# TIDA-01576_ADS8686S_AFE_Pg3-eFuse_3_3V_D.net
KiCad netlist of a schematic drawn in Altium Designer
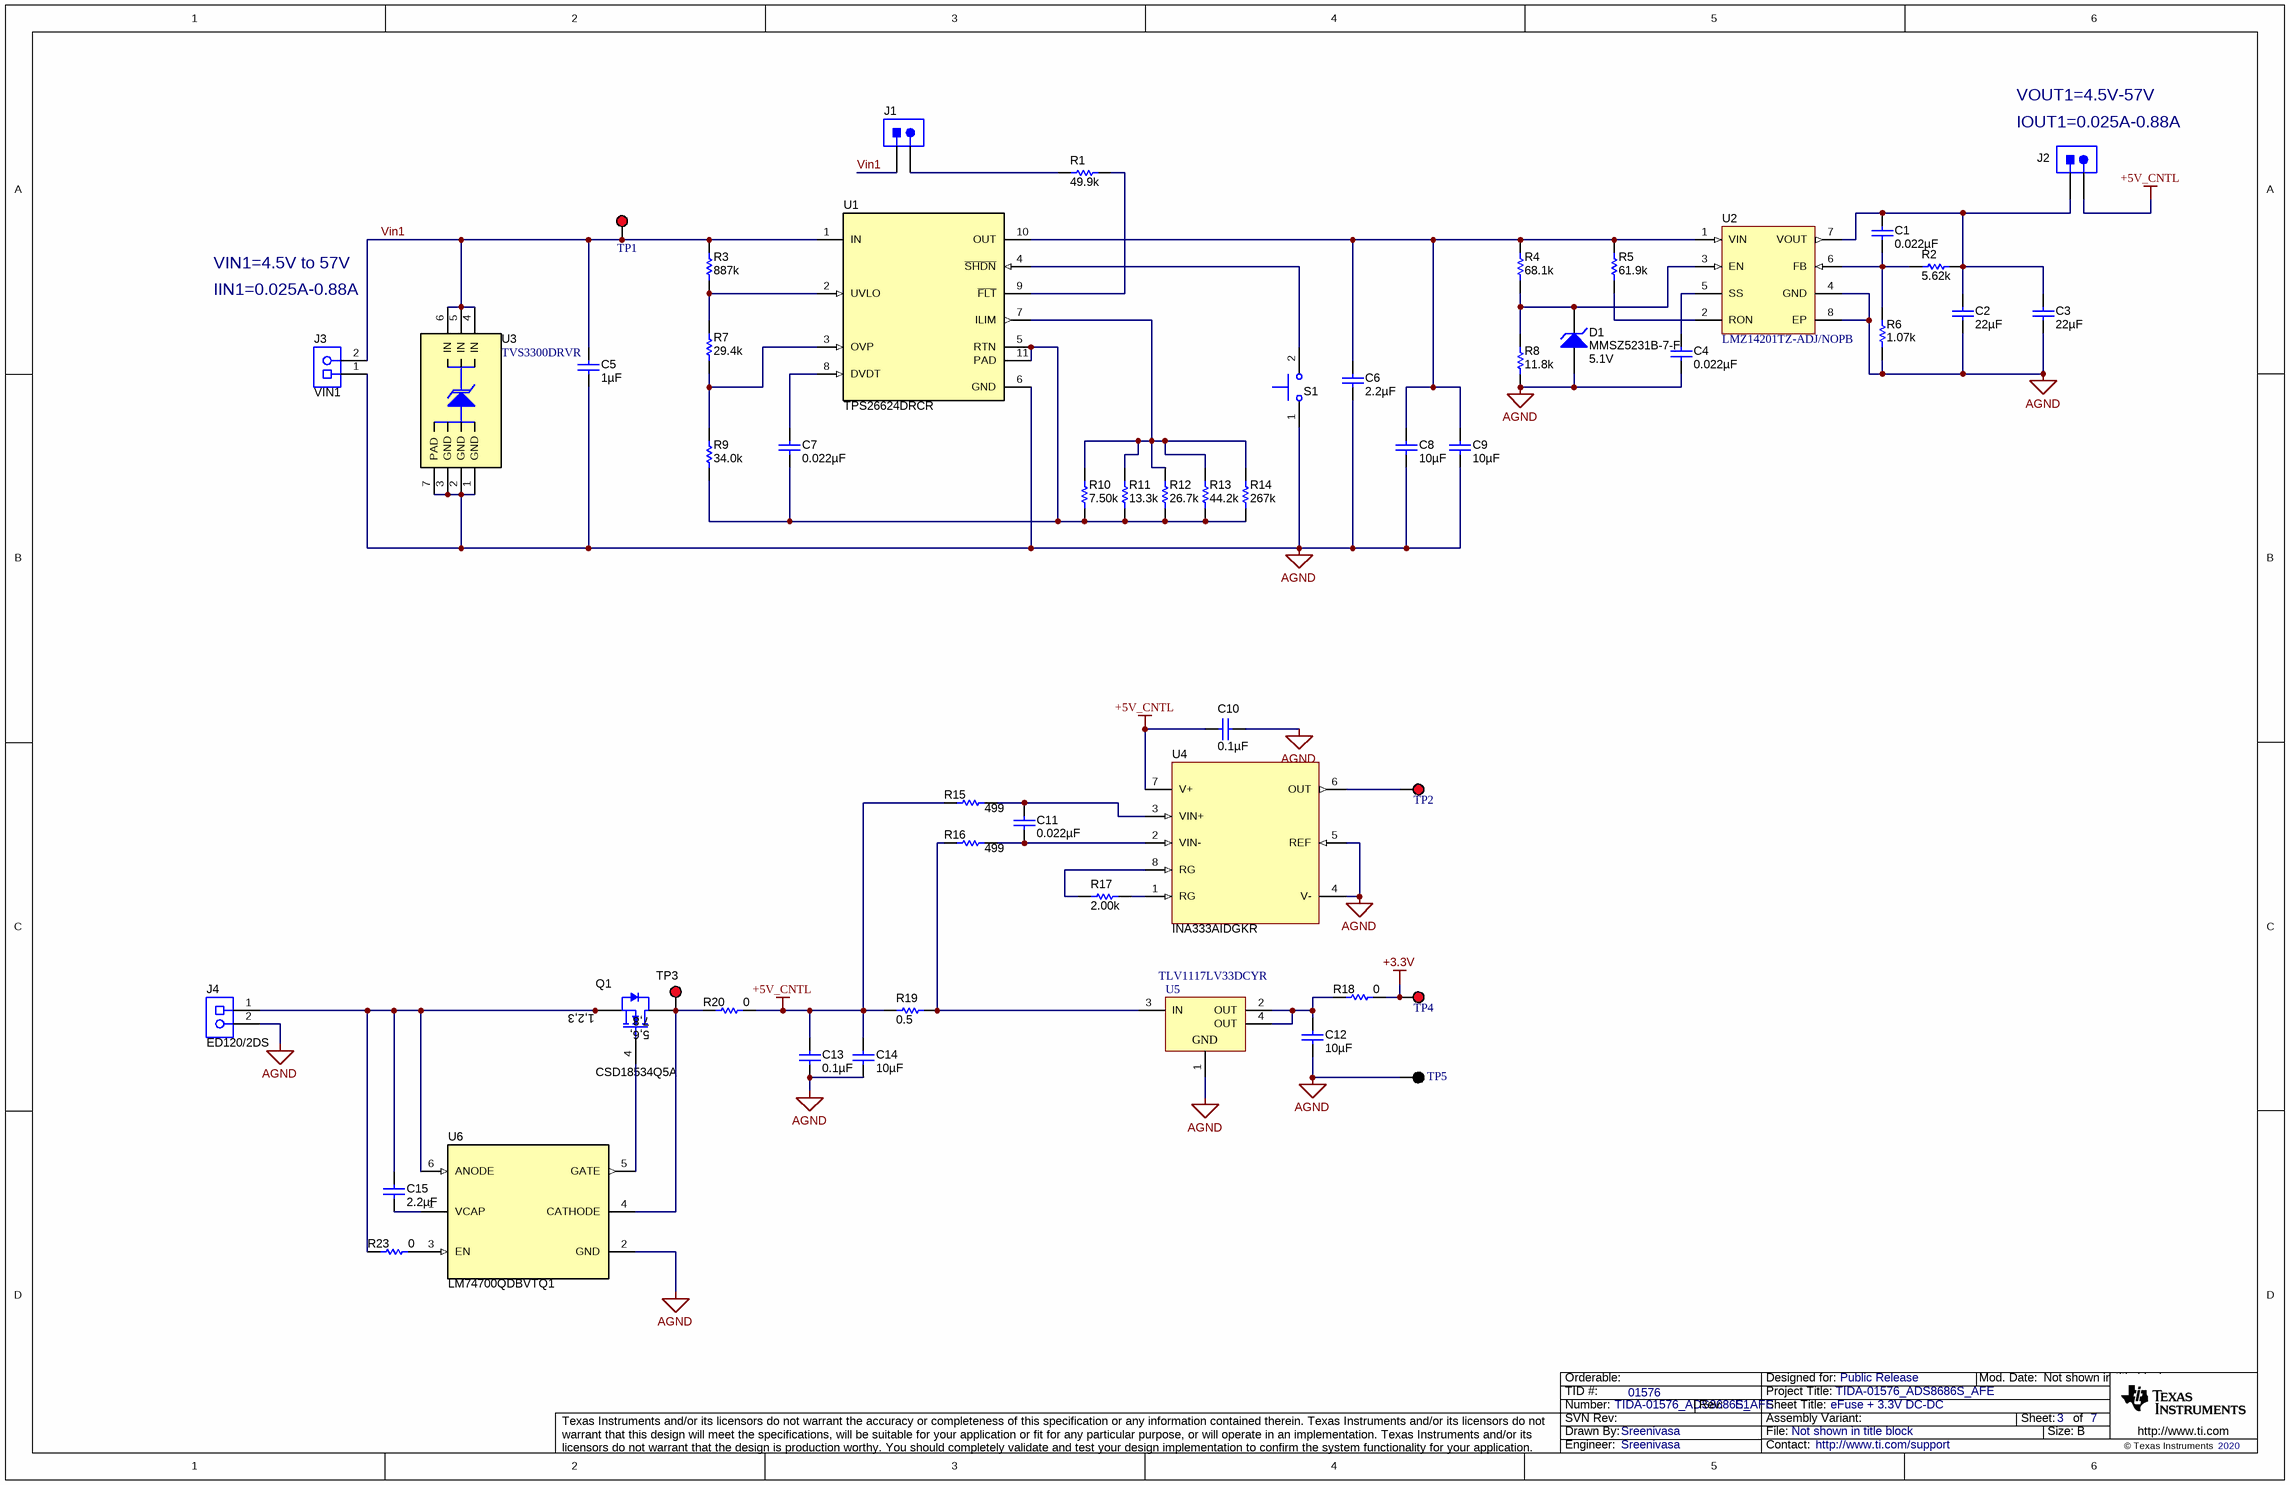
[diagram p0: TIDA-01576_ADS8686S_AFE_Pg3-eFuse + 3.3V DC-DC.SchDoc]

(export (version "E")
  (design (tool "Eeschema 10.0.6"))
  (components
    (comp (ref "C1")
      (value "C0603C223K4RACTU")
      (footprint "0603")
      (description "CAP, CERM, 0.022 µF, 16 V,+/- 10%, X7R, 0603")
      (fields
        (field (name "VALUEDISPLAYED") "0.022µF")
        (field (name "MANUFACTURER") "Kemet")
        (field (name "PUBLISHER") "Texas Instruments")
      )
      (libsource (lib "Capacitor_Ceramic") (part "C0603C223K4RACTU"))
    )
    (comp (ref "C2")
      (value "EMK316BB7226ML-T")
      (footprint "1206_190")
      (description "CAP, CERM, 22 µF, 16 V,+/- 20%, X7R, 1206")
      (fields
        (field (name "VALUEDISPLAYED") "22µF")
        (field (name "MANUFACTURER") "Taiyo Yuden")
        (field (name "PUBLISHER") "Texas Instruments")
      )
      (libsource (lib "Capacitor_Ceramic") (part "EMK316BB7226ML-T"))
    )
    (comp (ref "C3")
      (value "EMK316BB7226ML-T")
      (footprint "1206_190")
      (description "CAP, CERM, 22 µF, 16 V,+/- 20%, X7R, 1206")
      (fields
        (field (name "VALUEDISPLAYED") "22µF")
        (field (name "MANUFACTURER") "Taiyo Yuden")
        (field (name "PUBLISHER") "Texas Instruments")
      )
      (libsource (lib "Capacitor_Ceramic") (part "EMK316BB7226ML-T"))
    )
    (comp (ref "C4")
      (value "C0603C223K4RACTU")
      (footprint "0603")
      (description "CAP, CERM, 0.022 µF, 16 V,+/- 10%, X7R, 0603")
      (fields
        (field (name "VALUEDISPLAYED") "0.022µF")
        (field (name "MANUFACTURER") "Kemet")
        (field (name "PUBLISHER") "Texas Instruments")
      )
      (libsource (lib "Capacitor_Ceramic") (part "C0603C223K4RACTU"))
    )
    (comp (ref "C5")
      (value "GRM31CR72A105KA01L")
      (footprint "1206_180M")
      (description "CAP, CERM, 1 µF, 100 V, +/- 10%, X7R, 1206")
      (fields
        (field (name "VALUEDISPLAYED") "1µF")
        (field (name "MANUFACTURER") "MuRata")
        (field (name "PUBLISHER") "Texas Instruments")
      )
      (libsource (lib "Capacitor_Ceramic") (part "GRM31CR72A105KA01L"))
    )
    (comp (ref "C6")
      (value "GRM32ER72A225KA35L")
      (footprint "1210_270")
      (description "CAP, CERM, 2.2 µF, 100 V, +/- 10%, X7R, 1210")
      (fields
        (field (name "VALUEDISPLAYED") "2.2µF")
        (field (name "MANUFACTURER") "MuRata")
        (field (name "PUBLISHER") "Texas Instruments")
      )
      (libsource (lib "Capacitor_Ceramic") (part "GRM32ER72A225KA35L"))
    )
    (comp (ref "C7")
      (value "GRM188R71C223KA01D")
      (footprint "0603")
      (description "CAP, CERM, 0.022 µF, 16 V,+/- 10%, X7R, 0603")
      (fields
        (field (name "VALUEDISPLAYED") "0.022µF")
        (field (name "MANUFACTURER") "MuRata")
        (field (name "PUBLISHER") "Texas Instruments")
      )
      (libsource (lib "Capacitor_Ceramic") (part "GRM188R71C223KA01D"))
    )
    (comp (ref "C8")
      (value "GRM32ER71J106KA12L")
      (footprint "1210_270")
      (description "CAP, CERM, 10 µF, 63 V, +/- 10%, X7R, 1210")
      (fields
        (field (name "VALUEDISPLAYED") "10µF")
        (field (name "MANUFACTURER") "MuRata")
        (field (name "PUBLISHER") "Texas Instruments")
      )
      (libsource (lib "Capacitor_Ceramic") (part "GRM32ER71J106KA12L"))
    )
    (comp (ref "C9")
      (value "GRM32ER71J106KA12L")
      (footprint "1210_270")
      (description "CAP, CERM, 10 µF, 63 V, +/- 10%, X7R, 1210")
      (fields
        (field (name "VALUEDISPLAYED") "10µF")
        (field (name "MANUFACTURER") "MuRata")
        (field (name "PUBLISHER") "Texas Instruments")
      )
      (libsource (lib "Capacitor_Ceramic") (part "GRM32ER71J106KA12L"))
    )
    (comp (ref "C10")
      (value "06033C104JAT2A")
      (footprint "0603M")
      (description "CAP, CERM, 0.1uF, 25V, +/-5%, X7R, 0603")
      (fields
        (field (name "VALUEDISPLAYED") "0.1µF")
        (field (name "MANUFACTURER") "AVX")
        (field (name "PUBLISHER") "Texas Instruments")
      )
      (libsource (lib "Capacitor_Ceramic") (part "06033C104JAT2A"))
    )
    (comp (ref "C11")
      (value "C0603C223K3RACTU")
      (footprint "0603M")
      (description "CAP, CERM, 0.022uF, 25V, +/-10%, X7R, 0603")
      (fields
        (field (name "VALUEDISPLAYED") "0.022µF")
        (field (name "MANUFACTURER") "Kemet")
        (field (name "PUBLISHER") "Texas Instruments")
      )
      (libsource (lib "Capacitor_Ceramic") (part "C0603C223K3RACTU"))
    )
    (comp (ref "C12")
      (value "C0603C106M9PACTU")
      (footprint "0603")
      (description "CAP, CERM, 10 µF, 6.3 V, +/- 20%, X5R, 0603")
      (fields
        (field (name "VALUEDISPLAYED") "10µF")
        (field (name "MANUFACTURER") "Kemet")
        (field (name "PUBLISHER") "Texas Instruments")
      )
      (libsource (lib "Capacitor_Ceramic") (part "C0603C106M9PACTU"))
    )
    (comp (ref "C13")
      (value "C0603C104K5RACTU")
      (footprint "0603")
      (description "CAP, CERM, 0.1uF, 50V, +/-10%, X7R, 0603")
      (fields
        (field (name "VALUEDISPLAYED") "0.1µF")
        (field (name "MANUFACTURER") "Kemet")
        (field (name "PUBLISHER") "Texas Instruments")
      )
      (libsource (lib "Capacitor_Ceramic") (part "C0603C104K5RACTU"))
    )
    (comp (ref "C14")
      (value "C0603C106M9PACTU")
      (footprint "0603")
      (description "CAP, CERM, 10 µF, 6.3 V, +/- 20%, X5R, 0603")
      (fields
        (field (name "VALUEDISPLAYED") "10µF")
        (field (name "MANUFACTURER") "Kemet")
        (field (name "PUBLISHER") "Texas Instruments")
      )
      (libsource (lib "Capacitor_Ceramic") (part "C0603C106M9PACTU"))
    )
    (comp (ref "C15")
      (value "C0805C225K8RACTU")
      (footprint "0805_HV")
      (description "CAP, CERM, 2.2uF, 10V, +/-10%, X7R, 0805")
      (fields
        (field (name "VALUEDISPLAYED") "2.2µF")
        (field (name "MANUFACTURER") "Kemet")
        (field (name "PUBLISHER") "Texas Instruments")
      )
      (libsource (lib "Capacitor_Ceramic") (part "C0805C225K8RACTU"))
    )
    (comp (ref "D1")
      (value "MMSZ5231B-7-F")
      (footprint "SOD-123")
      (description "Diode, Zener, 5.1 V, 500 mW, SOD-123")
      (fields
        (field (name "ALTIUM_VALUE") "5.1V")
        (field (name "MANUFACTURER") "Diodes Inc.")
        (field (name "SYMBOLCREATOR") "a0412235")
        (field (name "PUBLISHER") "Texas Instruments")
      )
      (libsource (lib "ZenerDiodes") (part "MMSZ5231B-7-F"))
    )
    (comp (ref "J1")
      (value "PBC02SAAN")
      (footprint "Sullins_PBC02SAAN")
      (description "Header, 100mil, 2x1, Gold, TH")
      (fields
        (field (name "MANUFACTURER") "Sullins Connector Solutions")
        (field (name "PUBLISHER") "Texas Instruments")
        (field (name "SYMBOLCREATOR") "a0412235")
      )
      (libsource (lib "Connectors_Sullins") (part "PBC02SAAN"))
    )
    (comp (ref "J2")
      (value "PBC02SAAN")
      (footprint "Sullins_PBC02SAAN")
      (description "Header, 100mil, 2x1, Gold, TH")
      (fields
        (field (name "MANUFACTURER") "Sullins Connector Solutions")
        (field (name "PUBLISHER") "Texas Instruments")
        (field (name "SYMBOLCREATOR") "a0412235")
      )
      (libsource (lib "Connectors_Sullins") (part "PBC02SAAN"))
    )
    (comp (ref "J3")
      (value "VIN1")
      (footprint "TEC_282841-2")
      (description "Terminal Block, 2x1, 5.08mm, TH")
      (fields
        (field (name "MANUFACTURER") "TE Connectivity")
        (field (name "PARTNUMBER") "282841-2")
        (field (name "PUBLISHER") "Texas Instruments")
      )
      (libsource (lib "Altium Vault - TI") (part "CMP-0054973-1"))
    )
    (comp (ref "J4")
      (value "ED120/2DS")
      (footprint "CONN_ED120-2DS")
      (description "TERMINAL BLOCK 5.08MM VERT 2POS, TH")
      (fields
        (field (name "MANUFACTURER") "On-Shore Technology")
        (field (name "SYMBOLCREATOR") "a0412235")
        (field (name "PUBLISHER") "Texas Instruments")
      )
      (libsource (lib "Connectors") (part "ED120/2DS"))
    )
    (comp (ref "Q1")
      (value "CSD18534Q5A")
      (footprint "DQJ0008A")
      (description "MOSFET, N-CH, 60 V, 50 A, DQJ0008A (VSONP-8)")
      (fields
        (field (name "MANUFACTURER") "Texas Instruments")
        (field (name "PUBLISHER") "Texas Instruments")
      )
      (libsource (lib "Altium Vault - TI") (part "CMP-0000817-1"))
    )
    (comp (ref "R1")
      (value "CRCW060349K9FKEA")
      (footprint "0603")
      (description "RES, 49.9 k, 1%, 0.1 W, 0603")
      (fields
        (field (name "MANUFACTURER") "Vishay-Dale")
        (field (name "VALUEDISPLAYED") "49.9k")
        (field (name "PUBLISHER") "Texas Instruments")
      )
      (libsource (lib "Resistor_0603") (part "CRCW060349K9FKEA"))
    )
    (comp (ref "R2")
      (value "RC0603FR-075K62L")
      (footprint "0603")
      (description "RES, 5.62 k, 1%, 0.1 W, 0603")
      (fields
        (field (name "VALUEDISPLAYED") "5.62k")
        (field (name "MANUFACTURER") "Yageo America")
        (field (name "PUBLISHER") "Texas Instruments")
      )
      (libsource (lib "Resistor_0603") (part "RC0603FR-075K62L"))
    )
    (comp (ref "R3")
      (value "CRCW0603887KFKEA")
      (footprint "0603")
      (description "RES, 887 k, 1%, 0.1 W, 0603")
      (fields
        (field (name "VALUEDISPLAYED") "887k")
        (field (name "MANUFACTURER") "Vishay-Dale")
        (field (name "PUBLISHER") "Texas Instruments")
      )
      (libsource (lib "Resistor_0603") (part "CRCW0603887KFKEA"))
    )
    (comp (ref "R4")
      (value "CRCW120668K1FKEA")
      (footprint "1206")
      (description "RES, 68.1 k, 1%, 0.25 W, 1206")
      (fields
        (field (name "VALUEDISPLAYED") "68.1k")
        (field (name "MANUFACTURER") "Vishay-Dale")
        (field (name "PUBLISHER") "Texas Instruments")
      )
      (libsource (lib "Resistor_1206") (part "CRCW120668K1FKEA"))
    )
    (comp (ref "R5")
      (value "RC1206FR-0761K9L")
      (footprint "1206")
      (description "RES, 61.9 k, 1%, 0.25 W, 1206")
      (fields
        (field (name "VALUEDISPLAYED") "61.9k")
        (field (name "MANUFACTURER") "Yageo America")
        (field (name "PUBLISHER") "Texas Instruments")
      )
      (libsource (lib "Resistor_1206") (part "RC1206FR-0761K9L"))
    )
    (comp (ref "R6")
      (value "ERA-3AEB1071V")
      (footprint "0603")
      (description "RES SMD 1.07KOHM 0.1% 1/10W 0603")
      (fields
        (field (name "VALUEDISPLAYED") "1.07k")
        (field (name "MANUFACTURER") "Panasonic")
        (field (name "PUBLISHER") "Texas Instruments")
      )
      (libsource (lib "Resistor_0603") (part "RT0603DRE071K07L"))
    )
    (comp (ref "R7")
      (value "CRCW060329K4FKEA")
      (footprint "0603")
      (description "RES, 29.4 k, 1%, 0.1 W, 0603")
      (fields
        (field (name "VALUEDISPLAYED") "29.4k")
        (field (name "MANUFACTURER") "Vishay-Dale")
        (field (name "PUBLISHER") "Texas Instruments")
      )
      (libsource (lib "Resistor_0603") (part "CRCW060329K4FKEA"))
    )
    (comp (ref "R8")
      (value "CRCW120611K8FKEA")
      (footprint "1206")
      (description "RES, 11.8 k, 1%, 0.25 W, 1206")
      (fields
        (field (name "VALUEDISPLAYED") "11.8k")
        (field (name "MANUFACTURER") "Vishay-Dale")
        (field (name "PUBLISHER") "Texas Instruments")
      )
      (libsource (lib "Resistor_1206") (part "CRCW120611K8FKEA"))
    )
    (comp (ref "R9")
      (value "CRCW060334K0FKEA")
      (footprint "0603")
      (description "RES, 34.0 k, 1%, 0.1 W, 0603")
      (fields
        (field (name "MANUFACTURER") "Vishay-Dale")
        (field (name "VALUEDISPLAYED") "34.0k")
        (field (name "PUBLISHER") "Texas Instruments")
      )
      (libsource (lib "Resistor_0603") (part "CRCW060334K0FKEA"))
    )
    (comp (ref "R10")
      (value "CRCW06037K50FKEA")
      (footprint "0603")
      (description "RES, 7.50 k, 1%, 0.1 W, 0603")
      (fields
        (field (name "VALUEDISPLAYED") "7.50k")
        (field (name "MANUFACTURER") "Vishay-Dale")
        (field (name "PUBLISHER") "Texas Instruments")
      )
      (libsource (lib "Resistor_0603") (part "CRCW06037K50FKEA"))
    )
    (comp (ref "R11")
      (value "CRCW060313K3FKEA")
      (footprint "0603")
      (description "RES, 13.3 k, 1%, 0.1 W, 0603")
      (fields
        (field (name "VALUEDISPLAYED") "13.3k")
        (field (name "MANUFACTURER") "Vishay-Dale")
        (field (name "PUBLISHER") "Texas Instruments")
      )
      (libsource (lib "Resistor_0603") (part "CRCW060313K3FKEA"))
    )
    (comp (ref "R12")
      (value "CRCW060326K7FKEA")
      (footprint "0603")
      (description "RES, 26.7 k, 1%, 0.1 W, 0603")
      (fields
        (field (name "VALUEDISPLAYED") "26.7k")
        (field (name "MANUFACTURER") "Vishay-Dale")
        (field (name "PUBLISHER") "Texas Instruments")
      )
      (libsource (lib "Resistor_0603") (part "CRCW060326K7FKEA"))
    )
    (comp (ref "R13")
      (value "CRCW060344K2FKEA")
      (footprint "0603")
      (description "RES, 44.2 k, 1%, 0.1 W, 0603")
      (fields
        (field (name "VALUEDISPLAYED") "44.2k")
        (field (name "MANUFACTURER") "Vishay-Dale")
        (field (name "PUBLISHER") "Texas Instruments")
      )
      (libsource (lib "Resistor_0603") (part "CRCW060344K2FKEA"))
    )
    (comp (ref "R14")
      (value "CRCW0603267KFKEA")
      (footprint "0603")
      (description "RES, 267 k, 1%, 0.1 W, 0603")
      (fields
        (field (name "VALUEDISPLAYED") "267k")
        (field (name "MANUFACTURER") "Vishay-Dale")
        (field (name "PUBLISHER") "Texas Instruments")
      )
      (libsource (lib "Resistor_0603") (part "CRCW0603267KFKEA"))
    )
    (comp (ref "R15")
      (value "499")
      (footprint "0402M")
      (description "RES, 499 ohm, 1%, 0.063W, 0402")
      (fields
        (field (name "PARTNUMBER") "CRCW0402499RFKED")
        (field (name "MANUFACTURER") "Vishay-Dale")
        (field (name "PUBLISHER") "Texas Instruments")
      )
      (libsource (lib "Resistor_0402") (part "CRCW0402499RFKED"))
    )
    (comp (ref "R16")
      (value "499")
      (footprint "0402M")
      (description "RES, 499 ohm, 1%, 0.063W, 0402")
      (fields
        (field (name "PARTNUMBER") "CRCW0402499RFKED")
        (field (name "MANUFACTURER") "Vishay-Dale")
        (field (name "PUBLISHER") "Texas Instruments")
      )
      (libsource (lib "Resistor_0402") (part "CRCW0402499RFKED"))
    )
    (comp (ref "R17")
      (value "CRCW04022K00FKED")
      (footprint "0402")
      (description "RES, 2.00 k, 1%, 0.063 W, 0402")
      (fields
        (field (name "VALUEDISPLAYED") "2.00k")
        (field (name "MANUFACTURER") "Vishay-Dale")
        (field (name "PUBLISHER") "Texas Instruments")
      )
      (libsource (lib "Resistor_0402") (part "CRCW04022K00FKED"))
    )
    (comp (ref "R18")
      (value "0")
      (footprint "0603")
      (description "RES, 0 ohm, 5%, 0.1W, 0603")
      (fields
        (field (name "PARTNUMBER") "CRCW06030000Z0EA")
        (field (name "MANUFACTURER") "Vishay-Dale")
        (field (name "PUBLISHER") "Texas Instruments")
      )
      (libsource (lib "Resistor_0603") (part "CRCW06030000Z0EA"))
    )
    (comp (ref "R19")
      (value "RL1220S-R50-F")
      (footprint "RL1220")
      (description "RES, 0.5, 1%, 0.33 W, 0805")
      (fields
        (field (name "VALUEDISPLAYED") "0.5")
        (field (name "MANUFACTURER") "Susumu Co Ltd")
        (field (name "PUBLISHER") "Texas Instruments")
      )
      (libsource (lib "Resistor_0805") (part "RL1220S-R50-F"))
    )
    (comp (ref "R20")
      (value "0")
      (footprint "0603")
      (description "RES, 0 ohm, 5%, 0.1W, 0603")
      (fields
        (field (name "PARTNUMBER") "CRCW06030000Z0EA")
        (field (name "MANUFACTURER") "Vishay-Dale")
        (field (name "PUBLISHER") "Texas Instruments")
      )
      (libsource (lib "Resistor_0603") (part "CRCW06030000Z0EA"))
    )
    (comp (ref "R23")
      (value "0")
      (footprint "0603")
      (description "RES, 0 ohm, 5%, 0.1W, 0603")
      (fields
        (field (name "PARTNUMBER") "CRCW06030000Z0EA")
        (field (name "MANUFACTURER") "Vishay-Dale")
        (field (name "PUBLISHER") "Texas Instruments")
      )
      (libsource (lib "Resistor_0603") (part "CRCW06030000Z0EA"))
    )
    (comp (ref "S1")
      (value "PTS820 J20M SMTR LFS")
      (footprint "SW_PTS820")
      (description "Switch, SPST-NO,  Off-Mom, 0.05A, 12VDC, SMD")
      (fields
        (field (name "MANUFACTURER") "C&K Components")
        (field (name "SYMBOLCREATOR") "a0412235")
        (field (name "PUBLISHER") "Texas Instruments")
      )
      (libsource (lib "Switches") (part "PTS820 J20M SMTR LFS"))
    )
    (comp (ref "TP1")
      (value "5000")
      (footprint "Keystone5000")
      (description "Test Point, Miniature, Red, TH")
      (fields (field (name "MANUFACTURER") "Keystone") (field (name "PUBLISHER") "Texas Instruments"))
      (libsource (lib "Connectors_Keystone") (part "5000"))
    )
    (comp (ref "TP2")
      (value "5000")
      (footprint "Keystone5000")
      (description "Test Point, Miniature, Red, TH")
      (fields (field (name "MANUFACTURER") "Keystone") (field (name "PUBLISHER") "Texas Instruments"))
      (libsource (lib "Connectors_Keystone") (part "5000"))
    )
    (comp (ref "TP3")
      (value "5000")
      (footprint "Keystone5000")
      (description "Test Point, Miniature, Red, TH")
      (fields (field (name "MANUFACTURER") "Keystone") (field (name "PUBLISHER") "Texas Instruments"))
      (libsource (lib "Altium Vault - TI") (part "CMP-0055137-1"))
    )
    (comp (ref "TP4")
      (value "5000")
      (footprint "Keystone5000")
      (description "Test Point, Miniature, Red, TH")
      (fields (field (name "MANUFACTURER") "Keystone") (field (name "PUBLISHER") "Texas Instruments"))
      (libsource (lib "Connectors_Keystone") (part "5000"))
    )
    (comp (ref "TP5")
      (value "5001")
      (footprint "Keystone5001")
      (description "Test Point, Miniature, Black, TH")
      (fields (field (name "MANUFACTURER") "Keystone") (field (name "PUBLISHER") "Texas Instruments"))
      (libsource (lib "Connectors_Keystone") (part "5001"))
    )
    (comp (ref "U1")
      (value "TPS26624DRCR")
      (footprint "DRC0010J")
      (description "7V - 57V, 800mA Industrial eFuse with Integrated Reverse Polarity Protection, DRC0010J (VSON-10)")
      (fields
        (field (name "ALTERNATE PARTNUMBER") "TPS26625DRCR")
        (field (name "MANUFACTURER") "Texas Instruments")
        (field (name "SYMBOLCREATOR") "a0411947")
        (field (name "PUBLISHER") "Texas Instruments")
      )
      (libsource (lib "TI_Pre_RTM") (part "TPS26624DRCR"))
    )
    (comp (ref "U2")
      (value "LMZ14201TZ-ADJ/NOPB")
      (footprint "TZA07A_V")
      (description "1A SIMPLE SWITCHER® Power Module with 42V Maximum Input, 7 pin TO-PMOD")
      (fields (field (name "MANUFACTURER") "Texas Instruments") (field (name "PUBLISHER") "Altium Limited"))
      (libsource (lib "NSC Switcher") (part "LMZ14201TZ-ADJ/NOPB"))
    )
    (comp (ref "U3")
      (value "TVS3300DRVR")
      (footprint "DRV0006A")
      (description "33-V Precision Surge Protection Clamp, DRV0006A (WSON-6)")
      (fields
        (field (name "PARTNUMBER") "TVS3300DRVR")
        (field (name "MANUFACTURER") "Texas Instruments")
        (field (name "ALTERNATE PARTNUMBER") "TVS3300DRVT")
      )
      (libsource (lib "Altium Vault - TI") (part "TVS3300DRV"))
    )
    (comp (ref "U4")
      (value "INA333AIDGKR")
      (footprint "DGK0008A_N")
      (description "Low-Power, Zero-Drift, Precision Instrumentation Amplifier, DGK0008A (VSSOP-8)")
      (fields
        (field (name "ALTERNATE PARTNUMBER") "INA333AIDGKT")
        (field (name "MANUFACTURER") "Texas Instruments")
        (field (name "SYMBOLCREATOR") "a0799628")
        (field (name "PUBLISHER") "Texas Instruments")
      )
      (libsource (lib "TI_Pre_Release") (part "INA333AIDGKR"))
    )
    (comp (ref "U5")
      (value "TLV1117LV33DCYR")
      (footprint "DCY0004A_N")
      (fields (field (name "MANUFACTURER") "Texas Instruments") (field (name "PARTNUMBER") "TLV1117LV33DCYR"))
      (libsource (lib "Altium Vault - TI") (part "TI-TLV1117LV33DCY4"))
    )
    (comp (ref "U6")
      (value "LM74700QDBVTQ1")
      (footprint "DBV0006A_N")
      (description "Low Iq Always ON Smart Diode Controller, DBV0006A (SOT-23-6)")
      (fields
        (field (name "ALTERNATE PARTNUMBER") "LM74700QDBVRQ1")
        (field (name "MANUFACTURER") "Texas Instruments")
        (field (name "PARTNUMBER") "LM74700QDBVTQ1")
      )
      (libsource (lib "Altium Vault - TI") (part "LM74700DDC"))
    )
  )
  (nets
    (net (code "1") (name "+3.3V") (class "Default")
      (node (ref "R18") (pin "2") (pinfunction "2_2") (pintype "passive"))
      (node (ref "TP4") (pin "1") (pintype "passive"))
    )
    (net (code "2") (name "+5V_CNTL") (class "Default")
      (node (ref "C10") (pin "2") (pinfunction "2_2") (pintype "passive"))
      (node (ref "C13") (pin "1") (pinfunction "1_1") (pintype "passive"))
      (node (ref "C14") (pin "1") (pinfunction "1_1") (pintype "passive"))
      (node (ref "J2") (pin "2") (pinfunction "2_2") (pintype "passive"))
      (node (ref "R15") (pin "1") (pinfunction "1_1") (pintype "passive"))
      (node (ref "R19") (pin "1") (pinfunction "1_1") (pintype "passive"))
      (node (ref "R20") (pin "2") (pinfunction "2_2") (pintype "passive"))
      (node (ref "U4") (pin "7") (pinfunction "V+_7") (pintype "power_in"))
    )
    (net (code "3") (name "/Vin1") (class "Default")
      (node (ref "C5") (pin "1") (pinfunction "1_1") (pintype "passive"))
      (node (ref "J1") (pin "1") (pinfunction "1_1") (pintype "passive"))
      (node (ref "J3") (pin "2") (pinfunction "2_2") (pintype "passive"))
      (node (ref "R3") (pin "2") (pinfunction "2_2") (pintype "passive"))
      (node (ref "TP1") (pin "1") (pintype "passive"))
      (node (ref "U1") (pin "1") (pinfunction "IN_1") (pintype "power_in"))
      (node (ref "U3") (pin "4") (pinfunction "IN_4") (pintype "passive"))
      (node (ref "U3") (pin "5") (pinfunction "IN_5") (pintype "passive"))
      (node (ref "U3") (pin "6") (pinfunction "IN_6") (pintype "passive"))
    )
    (net (code "4") (name "AGND") (class "Default")
      (node (ref "C10") (pin "1") (pinfunction "1_1") (pintype "passive"))
      (node (ref "C12") (pin "2") (pinfunction "2_2") (pintype "passive"))
      (node (ref "C13") (pin "2") (pinfunction "2_2") (pintype "passive"))
      (node (ref "C14") (pin "2") (pinfunction "2_2") (pintype "passive"))
      (node (ref "C2") (pin "2") (pinfunction "2_2") (pintype "passive"))
      (node (ref "C3") (pin "2") (pinfunction "2_2") (pintype "passive"))
      (node (ref "C4") (pin "2") (pinfunction "2_2") (pintype "passive"))
      (node (ref "C5") (pin "2") (pinfunction "2_2") (pintype "passive"))
      (node (ref "C6") (pin "2") (pinfunction "2_2") (pintype "passive"))
      (node (ref "C8") (pin "2") (pinfunction "2_2") (pintype "passive"))
      (node (ref "C9") (pin "2") (pinfunction "2_2") (pintype "passive"))
      (node (ref "D1") (pin "2") (pinfunction "A_2") (pintype "passive"))
      (node (ref "J3") (pin "1") (pinfunction "1_1") (pintype "passive"))
      (node (ref "J4") (pin "2") (pinfunction "2_2") (pintype "passive"))
      (node (ref "R6") (pin "1") (pinfunction "1_1") (pintype "passive"))
      (node (ref "R8") (pin "1") (pinfunction "1_1") (pintype "passive"))
      (node (ref "S1") (pin "1") (pinfunction "1_1") (pintype "passive"))
      (node (ref "TP5") (pin "1") (pintype "passive"))
      (node (ref "U1") (pin "6") (pinfunction "GND_6") (pintype "power_in"))
      (node (ref "U2") (pin "4") (pinfunction "GND_4") (pintype "power_in"))
      (node (ref "U2") (pin "8") (pinfunction "EP_8") (pintype "passive"))
      (node (ref "U3") (pin "1") (pinfunction "GND_1") (pintype "passive"))
      (node (ref "U3") (pin "2") (pinfunction "GND_2") (pintype "passive"))
      (node (ref "U3") (pin "3") (pinfunction "GND_3") (pintype "passive"))
      (node (ref "U3") (pin "7") (pinfunction "PAD_7") (pintype "passive"))
      (node (ref "U4") (pin "4") (pinfunction "V-_4") (pintype "power_in"))
      (node (ref "U4") (pin "5") (pinfunction "REF_5") (pintype "input"))
      (node (ref "U5") (pin "1") (pinfunction "GND_1") (pintype "power_in"))
      (node (ref "U6") (pin "2") (pinfunction "GND_2") (pintype "passive"))
    )
    (net (code "5") (name "Net-(C12-Pad1)") (class "Default")
      (node (ref "C12") (pin "1") (pinfunction "1_1") (pintype "passive"))
      (node (ref "R18") (pin "1") (pinfunction "1_1") (pintype "passive"))
      (node (ref "U5") (pin "2") (pinfunction "OUT_2") (pintype "power_in"))
      (node (ref "U5") (pin "4") (pinfunction "OUT_4") (pintype "power_in"))
    )
    (net (code "6") (name "Net-(D1-K)") (class "Default")
      (node (ref "D1") (pin "1") (pinfunction "K_1") (pintype "passive"))
      (node (ref "R4") (pin "1") (pinfunction "1_1") (pintype "passive"))
      (node (ref "R8") (pin "2") (pinfunction "2_2") (pintype "passive"))
      (node (ref "U2") (pin "3") (pinfunction "EN_3") (pintype "input"))
    )
    (net (code "7") (name "Net-(J1-Pad2)") (class "Default")
      (node (ref "J1") (pin "2") (pinfunction "2_2") (pintype "passive"))
      (node (ref "R1") (pin "2") (pinfunction "2_2") (pintype "passive"))
    )
    (net (code "8") (name "Net-(Q1-G)") (class "Default")
      (node (ref "Q1") (pin "4") (pinfunction "G_4") (pintype "passive"))
      (node (ref "U6") (pin "5") (pinfunction "GATE_5") (pintype "output"))
    )
    (net (code "9") (name "Net-(R17-Pad1)") (class "Default")
      (node (ref "R17") (pin "1") (pinfunction "1_1") (pintype "passive"))
      (node (ref "U4") (pin "1") (pinfunction "RG_1") (pintype "input"))
    )
    (net (code "10") (name "Net-(R17-Pad2)") (class "Default")
      (node (ref "R17") (pin "2") (pinfunction "2_2") (pintype "passive"))
      (node (ref "U4") (pin "8") (pinfunction "RG_8") (pintype "input"))
    )
    (net (code "11") (name "Net-(U1-DVDT)") (class "Default")
      (node (ref "C7") (pin "1") (pinfunction "1_1") (pintype "passive"))
      (node (ref "U1") (pin "8") (pinfunction "DVDT_8") (pintype "input"))
    )
    (net (code "12") (name "Net-(U1-FLT)") (class "Default")
      (node (ref "R1") (pin "1") (pinfunction "1_1") (pintype "passive"))
      (node (ref "U1") (pin "9") (pinfunction "FLT_9") (pintype "open_collector"))
    )
    (net (code "13") (name "Net-(U1-ILIM)") (class "Default")
      (node (ref "R10") (pin "2") (pinfunction "2_2") (pintype "passive"))
      (node (ref "R11") (pin "2") (pinfunction "2_2") (pintype "passive"))
      (node (ref "R12") (pin "2") (pinfunction "2_2") (pintype "passive"))
      (node (ref "R13") (pin "2") (pinfunction "2_2") (pintype "passive"))
      (node (ref "R14") (pin "2") (pinfunction "2_2") (pintype "passive"))
      (node (ref "U1") (pin "7") (pinfunction "ILIM_7") (pintype "output"))
    )
    (net (code "14") (name "Net-(U1-OUT)") (class "Default")
      (node (ref "C6") (pin "1") (pinfunction "1_1") (pintype "passive"))
      (node (ref "C8") (pin "1") (pinfunction "1_1") (pintype "passive"))
      (node (ref "C9") (pin "1") (pinfunction "1_1") (pintype "passive"))
      (node (ref "R4") (pin "2") (pinfunction "2_2") (pintype "passive"))
      (node (ref "R5") (pin "2") (pinfunction "2_2") (pintype "passive"))
      (node (ref "U1") (pin "10") (pinfunction "OUT_10") (pintype "power_in"))
      (node (ref "U2") (pin "1") (pinfunction "VIN_1") (pintype "input"))
    )
    (net (code "15") (name "Net-(U1-OVP)") (class "Default")
      (node (ref "R7") (pin "1") (pinfunction "1_1") (pintype "passive"))
      (node (ref "R9") (pin "2") (pinfunction "2_2") (pintype "passive"))
      (node (ref "U1") (pin "3") (pinfunction "OVP_3") (pintype "input"))
    )
    (net (code "16") (name "Net-(U1-PAD)") (class "Default")
      (node (ref "C7") (pin "2") (pinfunction "2_2") (pintype "passive"))
      (node (ref "R10") (pin "1") (pinfunction "1_1") (pintype "passive"))
      (node (ref "R11") (pin "1") (pinfunction "1_1") (pintype "passive"))
      (node (ref "R12") (pin "1") (pinfunction "1_1") (pintype "passive"))
      (node (ref "R13") (pin "1") (pinfunction "1_1") (pintype "passive"))
      (node (ref "R14") (pin "1") (pinfunction "1_1") (pintype "passive"))
      (node (ref "R9") (pin "1") (pinfunction "1_1") (pintype "passive"))
      (node (ref "U1") (pin "11") (pinfunction "PAD_11") (pintype "power_in"))
      (node (ref "U1") (pin "5") (pinfunction "RTN_5") (pintype "passive"))
    )
    (net (code "17") (name "Net-(U1-SHDN)") (class "Default")
      (node (ref "S1") (pin "2") (pinfunction "2_2") (pintype "passive"))
      (node (ref "U1") (pin "4") (pinfunction "SHDN_4") (pintype "input"))
    )
    (net (code "18") (name "Net-(U1-UVLO)") (class "Default")
      (node (ref "R3") (pin "1") (pinfunction "1_1") (pintype "passive"))
      (node (ref "R7") (pin "2") (pinfunction "2_2") (pintype "passive"))
      (node (ref "U1") (pin "2") (pinfunction "UVLO_2") (pintype "input"))
    )
    (net (code "19") (name "Net-(U2-FB)") (class "Default")
      (node (ref "C1") (pin "2") (pinfunction "2_2") (pintype "passive"))
      (node (ref "R2") (pin "1") (pinfunction "1_1") (pintype "passive"))
      (node (ref "R6") (pin "2") (pinfunction "2_2") (pintype "passive"))
      (node (ref "U2") (pin "6") (pinfunction "FB_6") (pintype "input"))
    )
    (net (code "20") (name "Net-(U2-RON)") (class "Default")
      (node (ref "R5") (pin "1") (pinfunction "1_1") (pintype "passive"))
      (node (ref "U2") (pin "2") (pinfunction "RON_2") (pintype "passive"))
    )
    (net (code "21") (name "Net-(U2-SS)") (class "Default")
      (node (ref "C4") (pin "1") (pinfunction "1_1") (pintype "passive"))
      (node (ref "U2") (pin "5") (pinfunction "SS_5") (pintype "passive"))
    )
    (net (code "22") (name "Net-(U2-VOUT)") (class "Default")
      (node (ref "C1") (pin "1") (pinfunction "1_1") (pintype "passive"))
      (node (ref "C2") (pin "1") (pinfunction "1_1") (pintype "passive"))
      (node (ref "C3") (pin "1") (pinfunction "1_1") (pintype "passive"))
      (node (ref "J2") (pin "1") (pinfunction "1_1") (pintype "passive"))
      (node (ref "R2") (pin "2") (pinfunction "2_2") (pintype "passive"))
      (node (ref "U2") (pin "7") (pinfunction "VOUT_7") (pintype "output"))
    )
    (net (code "23") (name "Net-(U4-OUT)") (class "Default")
      (node (ref "TP2") (pin "1") (pintype "passive"))
      (node (ref "U4") (pin "6") (pinfunction "OUT_6") (pintype "output"))
    )
    (net (code "24") (name "Net-(U4-VIN+)") (class "Default")
      (node (ref "C11") (pin "1") (pinfunction "1_1") (pintype "passive"))
      (node (ref "R15") (pin "2") (pinfunction "2_2") (pintype "passive"))
      (node (ref "U4") (pin "3") (pinfunction "VIN+_3") (pintype "input"))
    )
    (net (code "25") (name "Net-(U4-VIN-)") (class "Default")
      (node (ref "C11") (pin "2") (pinfunction "2_2") (pintype "passive"))
      (node (ref "R16") (pin "2") (pinfunction "2_2") (pintype "passive"))
      (node (ref "U4") (pin "2") (pinfunction "VIN-_2") (pintype "input"))
    )
    (net (code "26") (name "Net-(U5-IN)") (class "Default")
      (node (ref "R16") (pin "1") (pinfunction "1_1") (pintype "passive"))
      (node (ref "R19") (pin "2") (pinfunction "2_2") (pintype "passive"))
      (node (ref "U5") (pin "3") (pinfunction "IN_3") (pintype "power_in"))
    )
    (net (code "27") (name "Net-(U6-ANODE)") (class "Default")
      (node (ref "C15") (pin "1") (pinfunction "1_1") (pintype "passive"))
      (node (ref "J4") (pin "1") (pinfunction "1_1") (pintype "passive"))
      (node (ref "Q1") (pin "1") (pinfunction "S_1") (pintype "passive"))
      (node (ref "Q1") (pin "2") (pinfunction "S_2") (pintype "passive"))
      (node (ref "Q1") (pin "3") (pinfunction "S_3") (pintype "passive"))
      (node (ref "R23") (pin "1") (pinfunction "1_1") (pintype "passive"))
      (node (ref "U6") (pin "6") (pinfunction "ANODE_6") (pintype "input"))
    )
    (net (code "28") (name "Net-(U6-CATHODE)") (class "Default")
      (node (ref "Q1") (pin "5") (pinfunction "D_5") (pintype "passive"))
      (node (ref "Q1") (pin "6") (pinfunction "D_6") (pintype "passive"))
      (node (ref "Q1") (pin "7") (pinfunction "D_7") (pintype "passive"))
      (node (ref "Q1") (pin "8") (pinfunction "D_8") (pintype "passive"))
      (node (ref "Q1") (pin "9") (pinfunction "D_9") (pintype "passive"))
      (node (ref "R20") (pin "1") (pinfunction "1_1") (pintype "passive"))
      (node (ref "TP3") (pin "1") (pintype "passive"))
      (node (ref "U6") (pin "4") (pinfunction "CATHODE_4") (pintype "power_in"))
    )
    (net (code "29") (name "Net-(U6-EN)") (class "Default")
      (node (ref "R23") (pin "2") (pinfunction "2_2") (pintype "passive"))
      (node (ref "U6") (pin "3") (pinfunction "EN_3") (pintype "input"))
    )
    (net (code "30") (name "Net-(U6-VCAP)") (class "Default")
      (node (ref "C15") (pin "2") (pinfunction "2_2") (pintype "passive"))
      (node (ref "U6") (pin "1") (pinfunction "VCAP_1") (pintype "power_in"))
    )
  )
)
